# 0_73OLED.net
KiCad netlist of a schematic drawn in Altium Designer
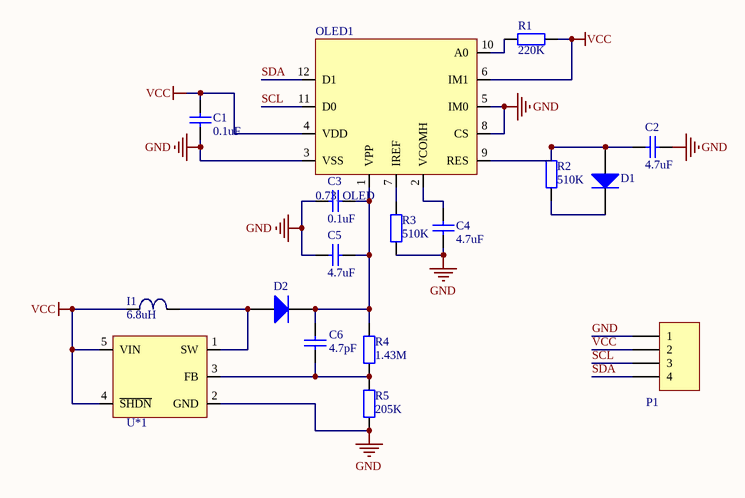
[diagram p0: 0.73OLED.SchDoc]

(export (version "E")
  (design (tool "Eeschema 10.0.6"))
  (components
    (comp (ref "C1")
      (value "0.1uF")
      (footprint "1__0603-CAP_")
      (description "Capacitor")
      (libsource (lib "Miscellaneous Devices") (part "Cap"))
    )
    (comp (ref "C2")
      (value "4.7uF")
      (footprint "1__0603-CAP_")
      (description "Capacitor")
      (libsource (lib "Miscellaneous Devices") (part "Cap"))
    )
    (comp (ref "C3")
      (value "0.1uF")
      (footprint "1__0603-CAP_")
      (description "Capacitor")
      (libsource (lib "Miscellaneous Devices") (part "Cap"))
    )
    (comp (ref "C4")
      (value "4.7uF")
      (footprint "1__0603-CAP_")
      (description "Capacitor")
      (libsource (lib "Miscellaneous Devices") (part "Cap"))
    )
    (comp (ref "C5")
      (value "4.7uF")
      (footprint "1__0603-CAP_")
      (description "Capacitor")
      (libsource (lib "Miscellaneous Devices") (part "Cap"))
    )
    (comp (ref "C6")
      (value "4.7pF")
      (footprint "1__0603-CAP_")
      (description "Capacitor")
      (libsource (lib "Miscellaneous Devices") (part "Cap"))
    )
    (comp (ref "D1")
      (value "Diode")
      (footprint "二极管1206")
      (description "Default Diode")
      (fields (field (name "PUBLISHER") "Altium Limited"))
      (libsource (lib "Miscellaneous Devices") (part "Diode"))
    )
    (comp (ref "D2")
      (value "Diode")
      (footprint "二极管1206")
      (description "Default Diode")
      (fields (field (name "PUBLISHER") "Altium Limited"))
      (libsource (lib "Miscellaneous Devices") (part "Diode"))
    )
    (comp (ref "I1") (value "6.8uH") (footprint "0805_Ind") (libsource (lib "常用原理图_by_K") (part "电感")))
    (comp (ref "OLED1")
      (value "0.73_OLED")
      (footprint "0.73OLED")
      (libsource (lib "原理图库") (part "0.73_OLED"))
    )
    (comp (ref "P1")
      (value "~")
      (footprint "HDR1X4")
      (description "Header, 4-Pin")
      (libsource (lib "!)Miscellaneous Integrated Library") (part "Header 4"))
    )
    (comp (ref "R1")
      (value "220K")
      (footprint "1__0603-RES_")
      (description "Resistor")
      (libsource (lib "") (part "Res2_1"))
    )
    (comp (ref "R2")
      (value "510K")
      (footprint "1__0603-RES_")
      (description "Resistor")
      (libsource (lib "Miscellaneous Devices") (part "Res2"))
    )
    (comp (ref "R3")
      (value "510K")
      (footprint "1__0603-RES_")
      (description "Resistor")
      (libsource (lib "Miscellaneous Devices") (part "Res2"))
    )
    (comp (ref "R4")
      (value "1.43M")
      (footprint "1__0603-RES_")
      (description "Resistor")
      (libsource (lib "Miscellaneous Devices") (part "Res2"))
    )
    (comp (ref "R5")
      (value "205K")
      (footprint "1__0603-RES_")
      (description "Resistor")
      (libsource (lib "Miscellaneous Devices") (part "Res2"))
    )
    (comp (ref "U*1") (value "OLED升压") (footprint "1__SOT23-5") (libsource (lib "原理图库") (part "TPS61040")))
  )
  (nets
    (net (code "1") (name "/SCL") (class "Default")
      (node (ref "OLED1") (pin "11") (pinfunction "D0_11") (pintype "passive"))
      (node (ref "P1") (pin "3") (pinfunction "3_3") (pintype "passive"))
    )
    (net (code "2") (name "/SDA") (class "Default")
      (node (ref "OLED1") (pin "12") (pinfunction "D1_12") (pintype "passive"))
      (node (ref "P1") (pin "4") (pinfunction "4_4") (pintype "passive"))
    )
    (net (code "3") (name "GND") (class "Default")
      (node (ref "C1") (pin "2") (pinfunction "2_2") (pintype "passive"))
      (node (ref "C2") (pin "2") (pinfunction "2_2") (pintype "passive"))
      (node (ref "C3") (pin "2") (pinfunction "2_2") (pintype "passive"))
      (node (ref "C4") (pin "2") (pinfunction "2_2") (pintype "passive"))
      (node (ref "C5") (pin "2") (pinfunction "2_2") (pintype "passive"))
      (node (ref "OLED1") (pin "3") (pinfunction "VSS_3") (pintype "passive"))
      (node (ref "OLED1") (pin "5") (pinfunction "IM0_5") (pintype "passive"))
      (node (ref "OLED1") (pin "8") (pinfunction "CS_8") (pintype "passive"))
      (node (ref "P1") (pin "1") (pinfunction "1_1") (pintype "passive"))
      (node (ref "R3") (pin "2") (pinfunction "2_2") (pintype "passive"))
      (node (ref "R5") (pin "2") (pinfunction "2_2") (pintype "passive"))
      (node (ref "U*1") (pin "2") (pinfunction "GND_2") (pintype "passive"))
    )
    (net (code "4") (name "Net-(D1-A)") (class "Default")
      (node (ref "C2") (pin "1") (pinfunction "1_1") (pintype "passive"))
      (node (ref "D1") (pin "1") (pinfunction "A_1") (pintype "passive"))
      (node (ref "OLED1") (pin "9") (pinfunction "RES_9") (pintype "passive"))
      (node (ref "R2") (pin "1") (pinfunction "1_1") (pintype "passive"))
    )
    (net (code "5") (name "Net-(D1-K)") (class "Default")
      (node (ref "D1") (pin "2") (pinfunction "K_2") (pintype "passive"))
      (node (ref "R2") (pin "2") (pinfunction "2_2") (pintype "passive"))
    )
    (net (code "6") (name "Net-(D2-A)") (class "Default")
      (node (ref "D2") (pin "1") (pinfunction "A_1") (pintype "passive"))
      (node (ref "I1") (pin "2") (pinfunction "2_2") (pintype "passive"))
      (node (ref "U*1") (pin "1") (pinfunction "SW_1") (pintype "passive"))
    )
    (net (code "7") (name "Net-(D2-K)") (class "Default")
      (node (ref "C3") (pin "1") (pinfunction "1_1") (pintype "passive"))
      (node (ref "C5") (pin "1") (pinfunction "1_1") (pintype "passive"))
      (node (ref "C6") (pin "2") (pinfunction "2_2") (pintype "passive"))
      (node (ref "D2") (pin "2") (pinfunction "K_2") (pintype "passive"))
      (node (ref "OLED1") (pin "1") (pinfunction "VPP_1") (pintype "passive"))
      (node (ref "R4") (pin "1") (pinfunction "1_1") (pintype "passive"))
    )
    (net (code "8") (name "Net-(OLED1-A0)") (class "Default")
      (node (ref "OLED1") (pin "10") (pinfunction "A0_10") (pintype "passive"))
      (node (ref "R1") (pin "1") (pinfunction "1_1") (pintype "passive"))
    )
    (net (code "9") (name "Net-(OLED1-IREF)") (class "Default")
      (node (ref "OLED1") (pin "7") (pinfunction "IREF_7") (pintype "passive"))
      (node (ref "R3") (pin "1") (pinfunction "1_1") (pintype "passive"))
    )
    (net (code "10") (name "Net-(OLED1-VCOMH)") (class "Default")
      (node (ref "C4") (pin "1") (pinfunction "1_1") (pintype "passive"))
      (node (ref "OLED1") (pin "2") (pinfunction "VCOMH_2") (pintype "passive"))
    )
    (net (code "11") (name "Net-(U*1-FB)") (class "Default")
      (node (ref "C6") (pin "1") (pinfunction "1_1") (pintype "passive"))
      (node (ref "R4") (pin "2") (pinfunction "2_2") (pintype "passive"))
      (node (ref "R5") (pin "1") (pinfunction "1_1") (pintype "passive"))
      (node (ref "U*1") (pin "3") (pinfunction "FB_3") (pintype "passive"))
    )
    (net (code "12") (name "VCC") (class "Default")
      (node (ref "C1") (pin "1") (pinfunction "1_1") (pintype "passive"))
      (node (ref "I1") (pin "1") (pinfunction "1_1") (pintype "passive"))
      (node (ref "OLED1") (pin "4") (pinfunction "VDD_4") (pintype "passive"))
      (node (ref "OLED1") (pin "6") (pinfunction "IM1_6") (pintype "passive"))
      (node (ref "P1") (pin "2") (pinfunction "2_2") (pintype "passive"))
      (node (ref "R1") (pin "2") (pinfunction "2_2") (pintype "passive"))
      (node (ref "U*1") (pin "4") (pinfunction "~{SHDN}_4") (pintype "passive"))
      (node (ref "U*1") (pin "5") (pinfunction "VIN_5") (pintype "passive"))
    )
  )
)
